# 1_Sheet_1_schdoc.net
KiCad netlist of a schematic drawn in Altium Designer
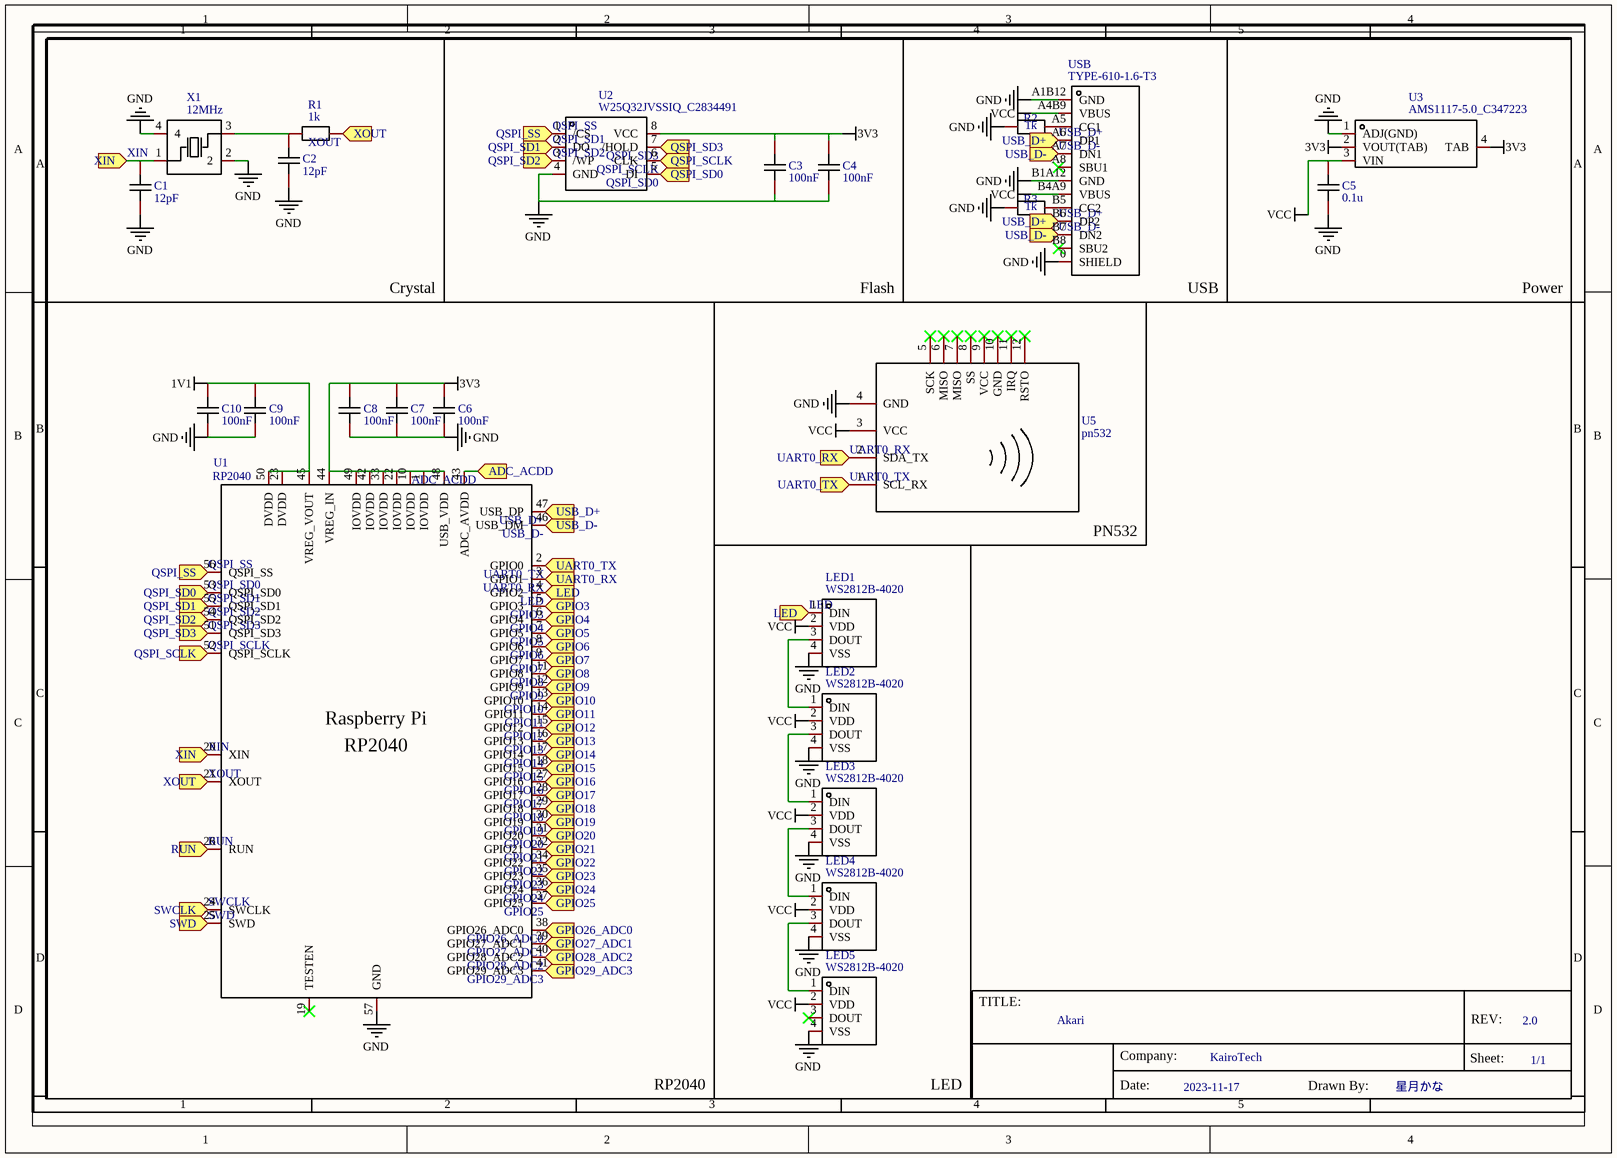
[diagram p0: 1_Sheet_1.schdoc.schdoc]

(export (version "E")
  (design (tool "Eeschema 10.0.6"))
  (components
    (comp (ref "C1")
      (value "12pF")
      (fields (field (name "NAME") "12pF"))
      (libsource (lib "altium-import") (part "root_1_12pF_"))
    )
    (comp (ref "C2")
      (value "12pF")
      (fields (field (name "NAME") "12pF"))
      (libsource (lib "altium-import") (part "root_3_12pF_"))
    )
    (comp (ref "C3")
      (value "100nF")
      (fields (field (name "NAME") "100nF"))
      (libsource (lib "altium-import") (part "root_1_100nF_"))
    )
    (comp (ref "C4")
      (value "100nF")
      (fields (field (name "NAME") "100nF"))
      (libsource (lib "altium-import") (part "root_1_100nF_"))
    )
    (comp (ref "C5")
      (value "0.1u")
      (fields (field (name "NAME") "0.1u"))
      (libsource (lib "altium-import") (part "root_3_0.1u_"))
    )
    (comp (ref "C6")
      (value "100nF")
      (fields (field (name "NAME") "100nF"))
      (libsource (lib "altium-import") (part "root_1_100nF_"))
    )
    (comp (ref "C7")
      (value "100nF")
      (fields (field (name "NAME") "100nF"))
      (libsource (lib "altium-import") (part "root_1_100nF_"))
    )
    (comp (ref "C8")
      (value "100nF")
      (fields (field (name "NAME") "100nF"))
      (libsource (lib "altium-import") (part "root_1_100nF_"))
    )
    (comp (ref "C9")
      (value "100nF")
      (fields (field (name "NAME") "100nF"))
      (libsource (lib "altium-import") (part "root_1_100nF_"))
    )
    (comp (ref "C10")
      (value "100nF")
      (fields (field (name "NAME") "100nF"))
      (libsource (lib "altium-import") (part "root_1_100nF_"))
    )
    (comp (ref "LED1")
      (value "WS2812B-4020")
      (fields (field (name "NAME") "WS2812B-4020") (field (name "MANUFACTURER") "worldsemi"))
      (libsource (lib "altium-import") (part "root_0_WS2812B-4020_"))
    )
    (comp (ref "LED2")
      (value "WS2812B-4020")
      (fields (field (name "NAME") "WS2812B-4020") (field (name "MANUFACTURER") "worldsemi"))
      (libsource (lib "altium-import") (part "root_0_WS2812B-4020_"))
    )
    (comp (ref "LED3")
      (value "WS2812B-4020")
      (fields (field (name "NAME") "WS2812B-4020") (field (name "MANUFACTURER") "worldsemi"))
      (libsource (lib "altium-import") (part "root_0_WS2812B-4020_"))
    )
    (comp (ref "LED4")
      (value "WS2812B-4020")
      (fields (field (name "NAME") "WS2812B-4020") (field (name "MANUFACTURER") "worldsemi"))
      (libsource (lib "altium-import") (part "root_0_WS2812B-4020_"))
    )
    (comp (ref "LED5")
      (value "WS2812B-4020")
      (fields (field (name "NAME") "WS2812B-4020") (field (name "MANUFACTURER") "worldsemi"))
      (libsource (lib "altium-import") (part "root_0_WS2812B-4020_"))
    )
    (comp (ref "R1")
      (value "1k")
      (fields (field (name "NAME") "1k"))
      (libsource (lib "altium-import") (part "root_0_1k_"))
    )
    (comp (ref "R2")
      (value "1k")
      (fields (field (name "NAME") "1k"))
      (libsource (lib "altium-import") (part "root_0_1k_"))
    )
    (comp (ref "R3")
      (value "1k")
      (fields (field (name "NAME") "1k"))
      (libsource (lib "altium-import") (part "root_0_1k_"))
    )
    (comp (ref "U1")
      (value "RP2040")
      (fields (field (name "NAME") "RP2040") (field (name "MANUFACTURER") "Raspberry Pi(树莓派)"))
      (libsource (lib "altium-import") (part "root_0_RP2040_"))
    )
    (comp (ref "U2")
      (value "W25Q32JVSSIQ_C2834491")
      (fields
        (field (name "NAME") "W25Q32JVSSIQ_C2834491")
        (field (name "MANUFACTURER") "WINBOND(华邦)")
        (field (name "MANUFACTURER PART") "W25Q32JVSSIQ")
      )
      (libsource (lib "altium-import") (part "root_0_W25Q32JVSSIQ_C2834491_"))
    )
    (comp (ref "U3")
      (value "AMS1117-5.0_C347223")
      (fields
        (field (name "NAME") "AMS1117-5.0_C347223")
        (field (name "MANUFACTURER") "UMW(广东友台半导体)")
        (field (name "MANUFACTURER PART") "AMS1117-5.0")
      )
      (libsource (lib "altium-import") (part "root_0_AMS1117-5.0_C347223_"))
    )
    (comp (ref "U5")
      (value "pn532")
      (fields (field (name "NAME") "pn532"))
      (libsource (lib "altium-import") (part "root_0_pn532_"))
    )
    (comp (ref "USB")
      (value "TYPE-610-1.6-T3")
      (fields (field (name "NAME") "TYPE-610-1.6-T3") (field (name "MANUFACTURER") "Yuandi(元迪)"))
      (libsource (lib "altium-import") (part "root_0_TYPE-610-1.6-T3_"))
    )
    (comp (ref "X1")
      (value "12MHz")
      (fields
        (field (name "NAME") "12MHz")
        (field (name "MANUFACTURER") "ABRACON")
        (field (name "MANUFACTURER PART") "ABM10AIG-12.000MHZ-4Z-T3")
      )
      (libsource (lib "altium-import") (part "root_0_12MHz_"))
    )
  )
  (nets
    (net (code "1") (name "/ADC_ACDD") (class "Default")
      (node (ref "U1") (pin "43") (pinfunction "ADC_AVDD_43") (pintype "passive"))
    )
    (net (code "2") (name "/GPIO3") (class "Default")
      (node (ref "U1") (pin "5") (pinfunction "GPIO3_5") (pintype "passive"))
    )
    (net (code "3") (name "/GPIO4") (class "Default")
      (node (ref "U1") (pin "6") (pinfunction "GPIO4_6") (pintype "passive"))
    )
    (net (code "4") (name "/GPIO5") (class "Default")
      (node (ref "U1") (pin "7") (pinfunction "GPIO5_7") (pintype "passive"))
    )
    (net (code "5") (name "/GPIO6") (class "Default")
      (node (ref "U1") (pin "8") (pinfunction "GPIO6_8") (pintype "passive"))
    )
    (net (code "6") (name "/GPIO7") (class "Default")
      (node (ref "U1") (pin "9") (pinfunction "GPIO7_9") (pintype "passive"))
    )
    (net (code "7") (name "/GPIO8") (class "Default")
      (node (ref "U1") (pin "11") (pinfunction "GPIO8_11") (pintype "passive"))
    )
    (net (code "8") (name "/GPIO9") (class "Default")
      (node (ref "U1") (pin "12") (pinfunction "GPIO9_12") (pintype "passive"))
    )
    (net (code "9") (name "/GPIO10") (class "Default")
      (node (ref "U1") (pin "13") (pinfunction "GPIO10_13") (pintype "passive"))
    )
    (net (code "10") (name "/GPIO11") (class "Default")
      (node (ref "U1") (pin "14") (pinfunction "GPIO11_14") (pintype "passive"))
    )
    (net (code "11") (name "/GPIO12") (class "Default")
      (node (ref "U1") (pin "15") (pinfunction "GPIO12_15") (pintype "passive"))
    )
    (net (code "12") (name "/GPIO13") (class "Default")
      (node (ref "U1") (pin "16") (pinfunction "GPIO13_16") (pintype "passive"))
    )
    (net (code "13") (name "/GPIO14") (class "Default")
      (node (ref "U1") (pin "17") (pinfunction "GPIO14_17") (pintype "passive"))
    )
    (net (code "14") (name "/GPIO15") (class "Default")
      (node (ref "U1") (pin "18") (pinfunction "GPIO15_18") (pintype "passive"))
    )
    (net (code "15") (name "/GPIO16") (class "Default")
      (node (ref "U1") (pin "27") (pinfunction "GPIO16_27") (pintype "passive"))
    )
    (net (code "16") (name "/GPIO17") (class "Default")
      (node (ref "U1") (pin "28") (pinfunction "GPIO17_28") (pintype "passive"))
    )
    (net (code "17") (name "/GPIO18") (class "Default")
      (node (ref "U1") (pin "29") (pinfunction "GPIO18_29") (pintype "passive"))
    )
    (net (code "18") (name "/GPIO19") (class "Default")
      (node (ref "U1") (pin "30") (pinfunction "GPIO19_30") (pintype "passive"))
    )
    (net (code "19") (name "/GPIO20") (class "Default")
      (node (ref "U1") (pin "31") (pinfunction "GPIO20_31") (pintype "passive"))
    )
    (net (code "20") (name "/GPIO21") (class "Default")
      (node (ref "U1") (pin "32") (pinfunction "GPIO21_32") (pintype "passive"))
    )
    (net (code "21") (name "/GPIO22") (class "Default")
      (node (ref "U1") (pin "34") (pinfunction "GPIO22_34") (pintype "passive"))
    )
    (net (code "22") (name "/GPIO23") (class "Default")
      (node (ref "U1") (pin "35") (pinfunction "GPIO23_35") (pintype "passive"))
    )
    (net (code "23") (name "/GPIO24") (class "Default")
      (node (ref "U1") (pin "36") (pinfunction "GPIO24_36") (pintype "passive"))
    )
    (net (code "24") (name "/GPIO25") (class "Default")
      (node (ref "U1") (pin "37") (pinfunction "GPIO25_37") (pintype "passive"))
    )
    (net (code "25") (name "/GPIO26_ADC0") (class "Default")
      (node (ref "U1") (pin "38") (pinfunction "GPIO26_ADC0_38") (pintype "passive"))
    )
    (net (code "26") (name "/GPIO27_ADC1") (class "Default")
      (node (ref "U1") (pin "39") (pinfunction "GPIO27_ADC1_39") (pintype "passive"))
    )
    (net (code "27") (name "/GPIO28_ADC2") (class "Default")
      (node (ref "U1") (pin "40") (pinfunction "GPIO28_ADC2_40") (pintype "passive"))
    )
    (net (code "28") (name "/GPIO29_ADC3") (class "Default")
      (node (ref "U1") (pin "41") (pinfunction "GPIO29_ADC3_41") (pintype "passive"))
    )
    (net (code "29") (name "/LED") (class "Default")
      (node (ref "LED1") (pin "1") (pinfunction "DIN_1") (pintype "passive"))
      (node (ref "U1") (pin "4") (pinfunction "GPIO2_4") (pintype "passive"))
    )
    (net (code "30") (name "/QSPI_SCLK") (class "Default")
      (node (ref "U1") (pin "52") (pinfunction "QSPI_SCLK_52") (pintype "passive"))
      (node (ref "U2") (pin "6") (pinfunction "CLK_6") (pintype "passive"))
    )
    (net (code "31") (name "/QSPI_SD0") (class "Default")
      (node (ref "U1") (pin "53") (pinfunction "QSPI_SD0_53") (pintype "passive"))
      (node (ref "U2") (pin "5") (pinfunction "DI_5") (pintype "passive"))
    )
    (net (code "32") (name "/QSPI_SD1") (class "Default")
      (node (ref "U1") (pin "55") (pinfunction "QSPI_SD1_55") (pintype "passive"))
      (node (ref "U2") (pin "2") (pinfunction "DO_2") (pintype "passive"))
    )
    (net (code "33") (name "/QSPI_SD2") (class "Default")
      (node (ref "U1") (pin "54") (pinfunction "QSPI_SD2_54") (pintype "passive"))
      (node (ref "U2") (pin "3") (pinfunction "/WP_3") (pintype "passive"))
    )
    (net (code "34") (name "/QSPI_SD3") (class "Default")
      (node (ref "U1") (pin "51") (pinfunction "QSPI_SD3_51") (pintype "passive"))
      (node (ref "U2") (pin "7") (pinfunction "/HOLD_7") (pintype "passive"))
    )
    (net (code "35") (name "/QSPI_SS") (class "Default")
      (node (ref "U1") (pin "56") (pinfunction "QSPI_SS_56") (pintype "passive"))
      (node (ref "U2") (pin "1") (pinfunction "/CS_1") (pintype "passive"))
    )
    (net (code "36") (name "/RUN") (class "Default")
      (node (ref "U1") (pin "26") (pinfunction "RUN_26") (pintype "passive"))
    )
    (net (code "37") (name "/SWCLK") (class "Default")
      (node (ref "U1") (pin "24") (pinfunction "SWCLK_24") (pintype "passive"))
    )
    (net (code "38") (name "/SWD") (class "Default")
      (node (ref "U1") (pin "25") (pinfunction "SWD_25") (pintype "passive"))
    )
    (net (code "39") (name "/UART0_RX") (class "Default")
      (node (ref "U1") (pin "3") (pinfunction "GPIO1_3") (pintype "passive"))
      (node (ref "U5") (pin "2") (pinfunction "SDA_TX_2") (pintype "passive"))
    )
    (net (code "40") (name "/UART0_TX") (class "Default")
      (node (ref "U1") (pin "2") (pinfunction "GPIO0_2") (pintype "passive"))
      (node (ref "U5") (pin "1") (pinfunction "SCL_RX_1") (pintype "passive"))
    )
    (net (code "41") (name "/USB_D+") (class "Default")
      (node (ref "U1") (pin "47") (pinfunction "USB_DP_47") (pintype "passive"))
      (node (ref "USB") (pin "A6") (pinfunction "DP1_A6") (pintype "passive"))
      (node (ref "USB") (pin "B6") (pinfunction "DP2_B6") (pintype "passive"))
    )
    (net (code "42") (name "/USB_D-") (class "Default")
      (node (ref "U1") (pin "46") (pinfunction "USB_DM_46") (pintype "passive"))
      (node (ref "USB") (pin "A7") (pinfunction "DN1_A7") (pintype "passive"))
      (node (ref "USB") (pin "B7") (pinfunction "DN2_B7") (pintype "passive"))
    )
    (net (code "43") (name "/XIN") (class "Default")
      (node (ref "C1") (pin "2") (pinfunction "2_2") (pintype "passive"))
      (node (ref "U1") (pin "20") (pinfunction "XIN_20") (pintype "passive"))
      (node (ref "X1") (pin "1") (pinfunction "OSC1_1") (pintype "passive"))
    )
    (net (code "44") (name "/XOUT") (class "Default")
      (node (ref "R1") (pin "2") (pinfunction "2_2") (pintype "passive"))
      (node (ref "U1") (pin "21") (pinfunction "XOUT_21") (pintype "passive"))
    )
    (net (code "45") (name "1V1") (class "Default")
      (node (ref "C10") (pin "2") (pinfunction "2_2") (pintype "passive"))
      (node (ref "C9") (pin "2") (pinfunction "2_2") (pintype "passive"))
      (node (ref "U1") (pin "23") (pinfunction "DVDD_23") (pintype "passive"))
      (node (ref "U1") (pin "45") (pinfunction "VREG_VOUT_45") (pintype "passive"))
      (node (ref "U1") (pin "50") (pinfunction "DVDD_50") (pintype "passive"))
    )
    (net (code "46") (name "3V3") (class "Default")
      (node (ref "C3") (pin "2") (pinfunction "2_2") (pintype "passive"))
      (node (ref "C4") (pin "2") (pinfunction "2_2") (pintype "passive"))
      (node (ref "C6") (pin "2") (pinfunction "2_2") (pintype "passive"))
      (node (ref "C7") (pin "2") (pinfunction "2_2") (pintype "passive"))
      (node (ref "C8") (pin "2") (pinfunction "2_2") (pintype "passive"))
      (node (ref "U1") (pin "1") (pinfunction "IOVDD_1") (pintype "passive"))
      (node (ref "U1") (pin "10") (pinfunction "IOVDD_10") (pintype "passive"))
      (node (ref "U1") (pin "22") (pinfunction "IOVDD_22") (pintype "passive"))
      (node (ref "U1") (pin "33") (pinfunction "IOVDD_33") (pintype "passive"))
      (node (ref "U1") (pin "42") (pinfunction "IOVDD_42") (pintype "passive"))
      (node (ref "U1") (pin "44") (pinfunction "VREG_IN_44") (pintype "passive"))
      (node (ref "U1") (pin "48") (pinfunction "USB_VDD_48") (pintype "passive"))
      (node (ref "U1") (pin "49") (pinfunction "IOVDD_49") (pintype "passive"))
      (node (ref "U2") (pin "8") (pinfunction "VCC_8") (pintype "passive"))
      (node (ref "U3") (pin "2") (pinfunction "VOUT(TAB)_2") (pintype "passive"))
      (node (ref "U3") (pin "4") (pinfunction "TAB_4") (pintype "passive"))
    )
    (net (code "47") (name "GND") (class "Default")
      (node (ref "C1") (pin "1") (pinfunction "1_1") (pintype "passive"))
      (node (ref "C10") (pin "1") (pinfunction "1_1") (pintype "passive"))
      (node (ref "C2") (pin "2") (pinfunction "2_2") (pintype "passive"))
      (node (ref "C3") (pin "1") (pinfunction "1_1") (pintype "passive"))
      (node (ref "C4") (pin "1") (pinfunction "1_1") (pintype "passive"))
      (node (ref "C5") (pin "2") (pinfunction "2_2") (pintype "passive"))
      (node (ref "C6") (pin "1") (pinfunction "1_1") (pintype "passive"))
      (node (ref "C7") (pin "1") (pinfunction "1_1") (pintype "passive"))
      (node (ref "C8") (pin "1") (pinfunction "1_1") (pintype "passive"))
      (node (ref "C9") (pin "1") (pinfunction "1_1") (pintype "passive"))
      (node (ref "LED1") (pin "4") (pinfunction "VSS_4") (pintype "passive"))
      (node (ref "LED2") (pin "4") (pinfunction "VSS_4") (pintype "passive"))
      (node (ref "LED3") (pin "4") (pinfunction "VSS_4") (pintype "passive"))
      (node (ref "LED4") (pin "4") (pinfunction "VSS_4") (pintype "passive"))
      (node (ref "LED5") (pin "4") (pinfunction "VSS_4") (pintype "passive"))
      (node (ref "R2") (pin "1") (pinfunction "1_1") (pintype "passive"))
      (node (ref "R3") (pin "1") (pinfunction "1_1") (pintype "passive"))
      (node (ref "U1") (pin "57") (pinfunction "GND_57") (pintype "passive"))
      (node (ref "U2") (pin "4") (pinfunction "GND_4") (pintype "passive"))
      (node (ref "U3") (pin "1") (pinfunction "ADJ(GND)_1") (pintype "passive"))
      (node (ref "U5") (pin "4") (pinfunction "GND_4") (pintype "passive"))
      (node (ref "USB") (pin "0") (pinfunction "SHIELD_0") (pintype "passive"))
      (node (ref "USB") (pin "A1B12") (pinfunction "GND_A1B12") (pintype "passive"))
      (node (ref "USB") (pin "B1A12") (pinfunction "GND_B1A12") (pintype "passive"))
      (node (ref "X1") (pin "2") (pinfunction "2_2") (pintype "passive"))
      (node (ref "X1") (pin "4") (pinfunction "4_4") (pintype "passive"))
    )
    (net (code "48") (name "Net-(LED1-DOUT)") (class "Default")
      (node (ref "LED1") (pin "3") (pinfunction "DOUT_3") (pintype "passive"))
      (node (ref "LED2") (pin "1") (pinfunction "DIN_1") (pintype "passive"))
    )
    (net (code "49") (name "Net-(LED2-DOUT)") (class "Default")
      (node (ref "LED2") (pin "3") (pinfunction "DOUT_3") (pintype "passive"))
      (node (ref "LED3") (pin "1") (pinfunction "DIN_1") (pintype "passive"))
    )
    (net (code "50") (name "Net-(LED3-DOUT)") (class "Default")
      (node (ref "LED3") (pin "3") (pinfunction "DOUT_3") (pintype "passive"))
      (node (ref "LED4") (pin "1") (pinfunction "DIN_1") (pintype "passive"))
    )
    (net (code "51") (name "Net-(LED4-DOUT)") (class "Default")
      (node (ref "LED4") (pin "3") (pinfunction "DOUT_3") (pintype "passive"))
      (node (ref "LED5") (pin "1") (pinfunction "DIN_1") (pintype "passive"))
    )
    (net (code "52") (name "Net-(USB-CC1)") (class "Default")
      (node (ref "R2") (pin "2") (pinfunction "2_2") (pintype "passive"))
      (node (ref "USB") (pin "A5") (pinfunction "CC1_A5") (pintype "passive"))
    )
    (net (code "53") (name "Net-(USB-CC2)") (class "Default")
      (node (ref "R3") (pin "2") (pinfunction "2_2") (pintype "passive"))
      (node (ref "USB") (pin "B5") (pinfunction "CC2_B5") (pintype "passive"))
    )
    (net (code "54") (name "Net-(X1-OSC2)") (class "Default")
      (node (ref "C2") (pin "1") (pinfunction "1_1") (pintype "passive"))
      (node (ref "R1") (pin "1") (pinfunction "1_1") (pintype "passive"))
      (node (ref "X1") (pin "3") (pinfunction "OSC2_3") (pintype "passive"))
    )
    (net (code "55") (name "VCC") (class "Default")
      (node (ref "C5") (pin "1") (pinfunction "1_1") (pintype "passive"))
      (node (ref "LED1") (pin "2") (pinfunction "VDD_2") (pintype "passive"))
      (node (ref "LED2") (pin "2") (pinfunction "VDD_2") (pintype "passive"))
      (node (ref "LED3") (pin "2") (pinfunction "VDD_2") (pintype "passive"))
      (node (ref "LED4") (pin "2") (pinfunction "VDD_2") (pintype "passive"))
      (node (ref "LED5") (pin "2") (pinfunction "VDD_2") (pintype "passive"))
      (node (ref "U3") (pin "3") (pinfunction "VIN_3") (pintype "passive"))
      (node (ref "U5") (pin "3") (pinfunction "VCC_3") (pintype "passive"))
      (node (ref "USB") (pin "A4B9") (pinfunction "VBUS_A4B9") (pintype "passive"))
      (node (ref "USB") (pin "B4A9") (pinfunction "VBUS_B4A9") (pintype "passive"))
    )
    (net (code "56") (name "unconnected-(LED5-DOUT-Pad3)") (class "Default")
      (node (ref "LED5") (pin "3") (pinfunction "DOUT_3") (pintype "passive+no_connect"))
    )
    (net (code "57") (name "unconnected-(U1-TESTEN-Pad19)") (class "Default")
      (node (ref "U1") (pin "19") (pinfunction "TESTEN_19") (pintype "passive+no_connect"))
    )
    (net (code "58") (name "unconnected-(U5-GND-Pad10)") (class "Default")
      (node (ref "U5") (pin "10") (pinfunction "GND_10") (pintype "passive+no_connect"))
    )
    (net (code "59") (name "unconnected-(U5-IRQ-Pad11)") (class "Default")
      (node (ref "U5") (pin "11") (pinfunction "IRQ_11") (pintype "passive+no_connect"))
    )
    (net (code "60") (name "unconnected-(U5-MISO-Pad6)") (class "Default")
      (node (ref "U5") (pin "6") (pinfunction "MISO_6") (pintype "passive+no_connect"))
    )
    (net (code "61") (name "unconnected-(U5-MISO-Pad7)") (class "Default")
      (node (ref "U5") (pin "7") (pinfunction "MISO_7") (pintype "passive+no_connect"))
    )
    (net (code "62") (name "unconnected-(U5-RSTO-Pad12)") (class "Default")
      (node (ref "U5") (pin "12") (pinfunction "RSTO_12") (pintype "passive+no_connect"))
    )
    (net (code "63") (name "unconnected-(U5-SCK-Pad5)") (class "Default")
      (node (ref "U5") (pin "5") (pinfunction "SCK_5") (pintype "passive+no_connect"))
    )
    (net (code "64") (name "unconnected-(U5-SS-Pad8)") (class "Default")
      (node (ref "U5") (pin "8") (pinfunction "SS_8") (pintype "passive+no_connect"))
    )
    (net (code "65") (name "unconnected-(U5-VCC-Pad9)") (class "Default")
      (node (ref "U5") (pin "9") (pinfunction "VCC_9") (pintype "passive+no_connect"))
    )
    (net (code "66") (name "unconnected-(USB-SBU1-PadA8)") (class "Default")
      (node (ref "USB") (pin "A8") (pinfunction "SBU1_A8") (pintype "passive+no_connect"))
    )
    (net (code "67") (name "unconnected-(USB-SBU2-PadB8)") (class "Default")
      (node (ref "USB") (pin "B8") (pinfunction "SBU2_B8") (pintype "passive+no_connect"))
    )
  )
)
